# Mozard.net
KiCad netlist of a schematic drawn in EAGLE
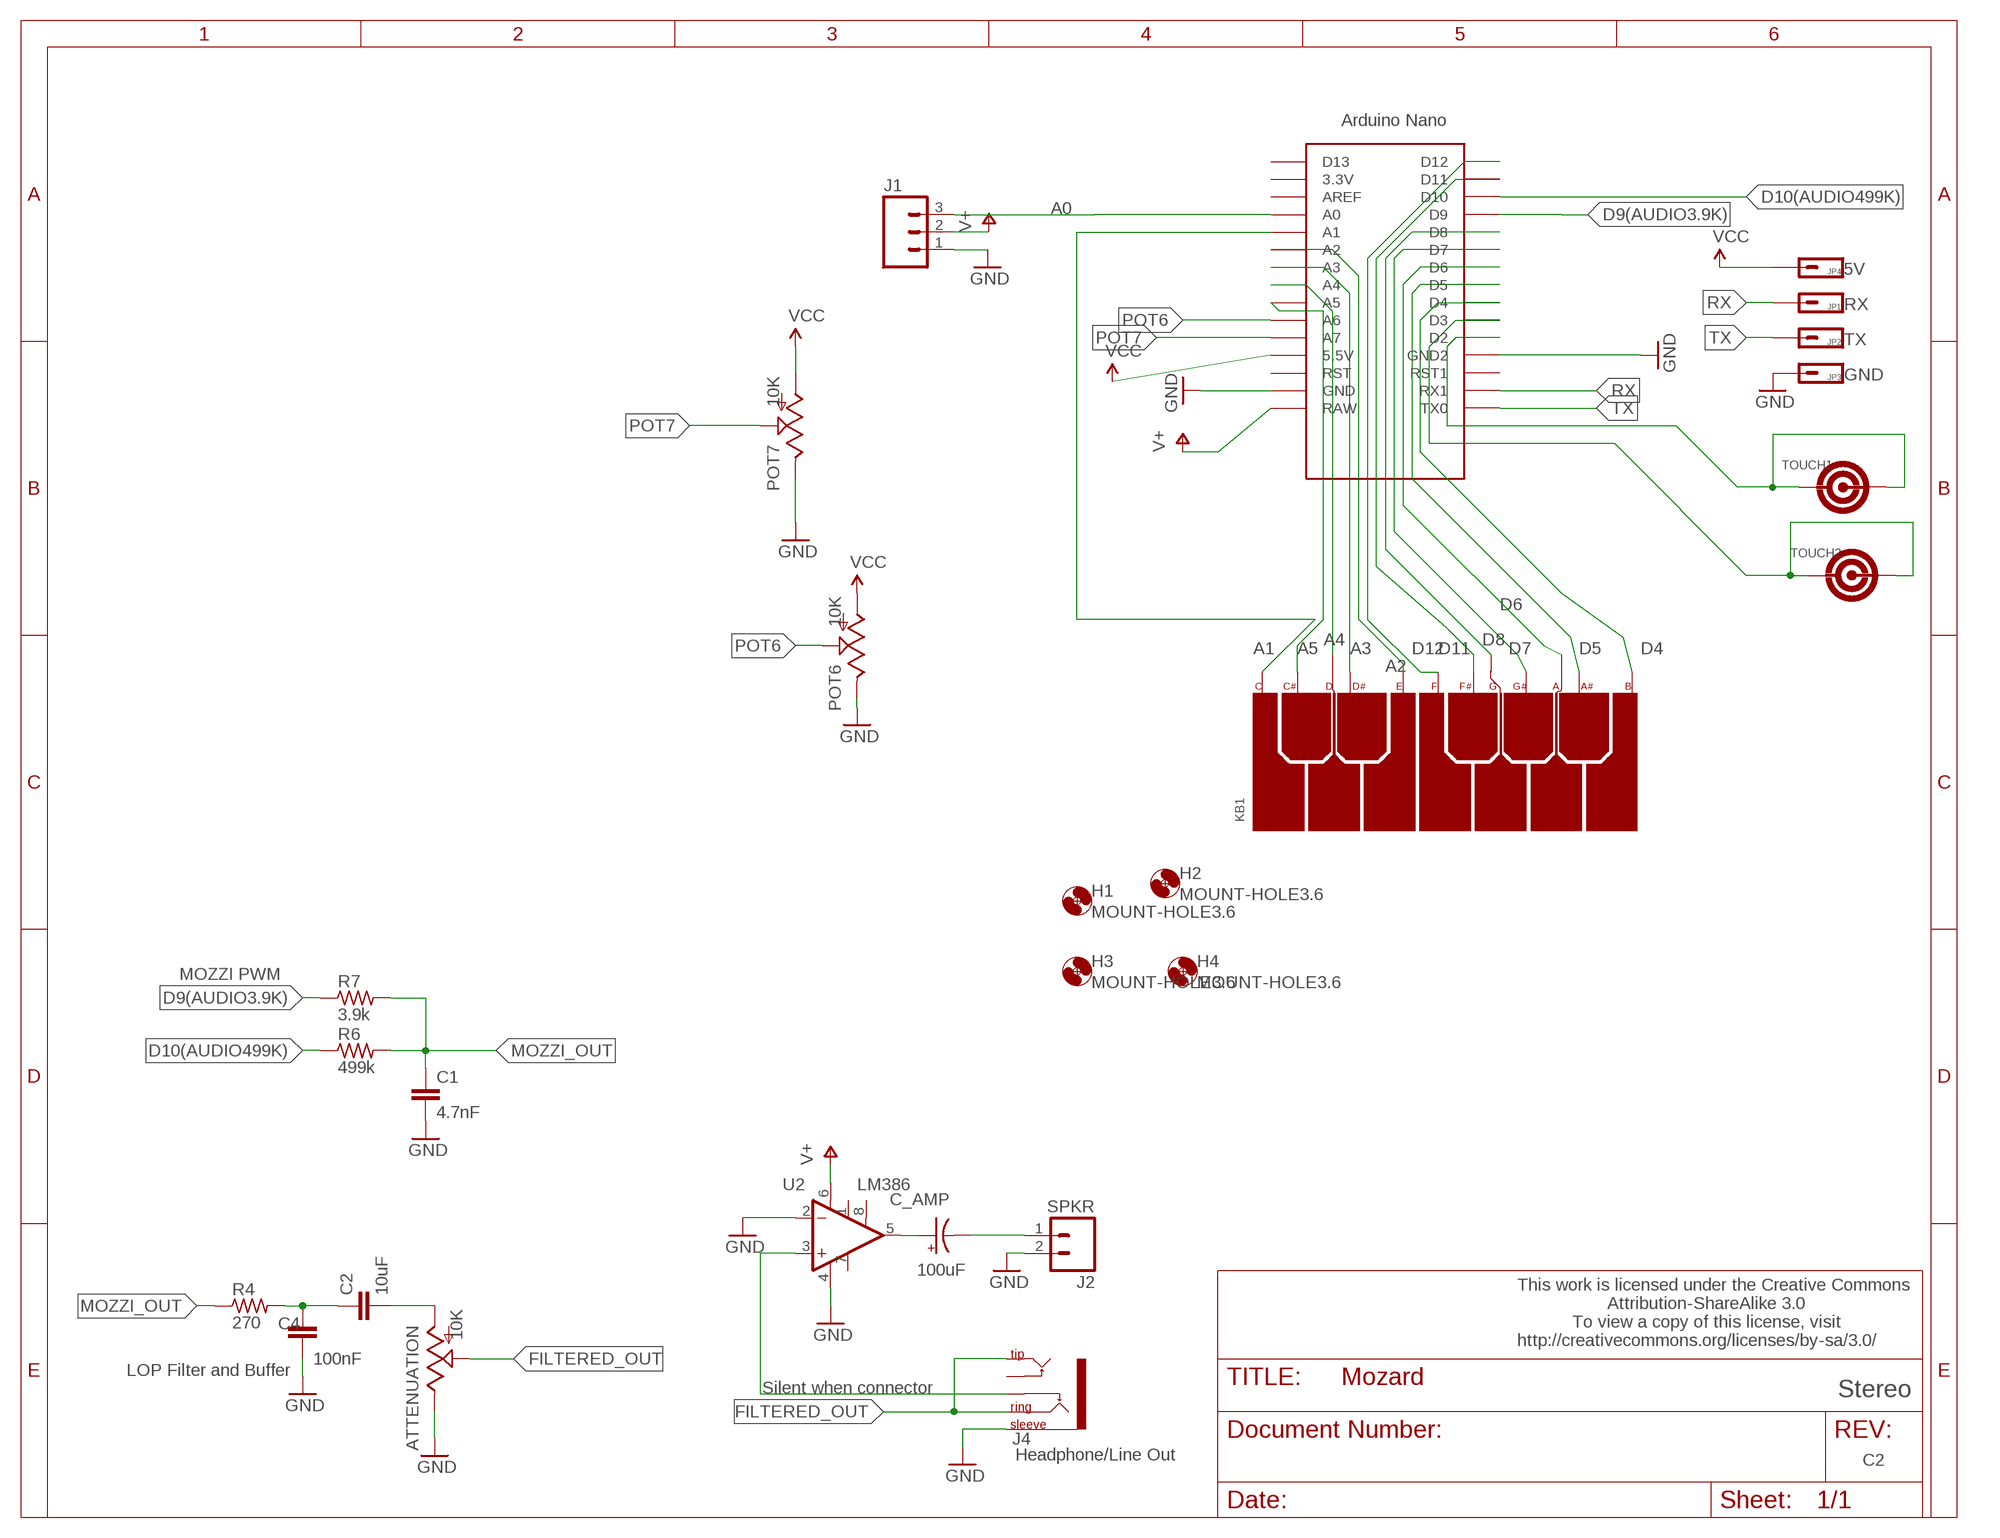
[diagram p0: schematic, sheet 1]

(export (version "E")
  (design (tool "Eeschema 10.0.6"))
  (components
    (comp (ref "ATTENUATION")
      (value "10K")
      (footprint "eagle-import:ALPS_POT_KIT")
      (libsource (lib "eagle-import") (part "POTALPS-KIT"))
    )
    (comp (ref "C1")
      (value "4.7nF")
      (footprint "eagle-import:CAP-PTH-SMALL-KIT")
      (libsource (lib "eagle-import") (part "0.1UF-50V-20%(PTH)KIT-EZ"))
    )
    (comp (ref "C2")
      (value "10uF")
      (footprint "eagle-import:CAP-PTH-SMALL-KIT")
      (libsource (lib "eagle-import") (part "0.1UF-50V-20%(PTH)KIT-EZ"))
    )
    (comp (ref "C4")
      (value "100nF")
      (footprint "eagle-import:CAP-PTH-SMALL-KIT")
      (libsource (lib "eagle-import") (part "0.1UF-50V-20%(PTH)KIT-EZ"))
    )
    (comp (ref "C_AMP")
      (value "100uF")
      (footprint "eagle-import:CPOL-RADIAL-10UF-25V")
      (libsource (lib "eagle-import") (part "CPOL-RADIAL-10UF-25V"))
    )
    (comp (ref "H1")
      (value "MOUNT-HOLE3.6")
      (footprint "eagle-import:3,6")
      (libsource (lib "eagle-import") (part "MOUNT-HOLE3.6"))
    )
    (comp (ref "H2")
      (value "MOUNT-HOLE3.6")
      (footprint "eagle-import:3,6")
      (libsource (lib "eagle-import") (part "MOUNT-HOLE3.6"))
    )
    (comp (ref "H3")
      (value "MOUNT-HOLE3.6")
      (footprint "eagle-import:3,6")
      (libsource (lib "eagle-import") (part "MOUNT-HOLE3.6"))
    )
    (comp (ref "H4")
      (value "MOUNT-HOLE3.6")
      (footprint "eagle-import:3,6")
      (libsource (lib "eagle-import") (part "MOUNT-HOLE3.6"))
    )
    (comp (ref "J1")
      (value "M03SCREW")
      (footprint "eagle-import:SCREWTERMINAL-3.5MM-3")
      (libsource (lib "eagle-import") (part "M03SCREW"))
    )
    (comp (ref "J2")
      (value "SPKR")
      (footprint "eagle-import:SCREWTERMINAL-3.5MM-2")
      (libsource (lib "eagle-import") (part "M023.5MM"))
    )
    (comp (ref "J4")
      (value "Headphone/Line Out")
      (footprint "eagle-import:AUDIO-JACK")
      (libsource (lib "eagle-import") (part "AUDIO-JACKPTH"))
    )
    (comp (ref "JP1")
      (value "RX")
      (footprint "eagle-import:1X01_SIDE_NAME")
      (libsource (lib "eagle-import") (part "HEADER-1X1"))
    )
    (comp (ref "JP2")
      (value "TX")
      (footprint "eagle-import:1X01_SIDE_NAME")
      (libsource (lib "eagle-import") (part "HEADER-1X1"))
    )
    (comp (ref "JP3")
      (value "GND")
      (footprint "eagle-import:1X01_SIDE_NAME")
      (libsource (lib "eagle-import") (part "HEADER-1X1"))
    )
    (comp (ref "JP4")
      (value "5V")
      (footprint "eagle-import:1X01_SIDE_NAME")
      (libsource (lib "eagle-import") (part "HEADER-1X1"))
    )
    (comp (ref "KB1")
      (value "PCB-KEYBOARD4")
      (footprint "eagle-import:PCB-KEYBOARD4")
      (libsource (lib "eagle-import") (part "PCB-KEYBOARD4"))
    )
    (comp (ref "POT6")
      (value "10K")
      (footprint "eagle-import:ALPS_POT_KIT")
      (libsource (lib "eagle-import") (part "POTALPS-KIT"))
    )
    (comp (ref "POT7")
      (value "10K")
      (footprint "eagle-import:ALPS_POT_KIT")
      (libsource (lib "eagle-import") (part "POTALPS-KIT"))
    )
    (comp (ref "R4")
      (value "270")
      (footprint "eagle-import:0204_7")
      (libsource (lib "eagle-import") (part "R-US_0204/7"))
    )
    (comp (ref "R6")
      (value "499k")
      (footprint "eagle-import:0204_7")
      (libsource (lib "eagle-import") (part "R-US_0204/7"))
    )
    (comp (ref "R7")
      (value "3.9k")
      (footprint "eagle-import:0204_7")
      (libsource (lib "eagle-import") (part "R-US_0204/7"))
    )
    (comp (ref "TOUCH1")
      (value "PCB-TOUCHPAD2")
      (footprint "eagle-import:PCB-TOUCHPAD2")
      (libsource (lib "eagle-import") (part "PCB-TOUCHPAD2"))
    )
    (comp (ref "TOUCH2")
      (value "PCB-TOUCHPAD2")
      (footprint "eagle-import:PCB-TOUCHPAD2")
      (libsource (lib "eagle-import") (part "PCB-TOUCHPAD2"))
    )
    (comp (ref "U$1")
      (value "NANO")
      (footprint "eagle-import:NANO")
      (libsource (lib "eagle-import") (part "NANO"))
    )
    (comp (ref "U2")
      (value "LM386")
      (footprint "eagle-import:DIP08")
      (libsource (lib "eagle-import") (part "LM386"))
    )
  )
  (nets
    (net (code "1") (name "/A0") (class "Default")
      (node (ref "J1") (pin "3") (pinfunction "3_3") (pintype "passive"))
      (node (ref "U$1") (pin "A0") (pinfunction "A0_A0") (pintype "bidirectional"))
    )
    (net (code "2") (name "/A1") (class "Default")
      (node (ref "KB1") (pin "C") (pinfunction "C_C") (pintype "bidirectional"))
      (node (ref "U$1") (pin "A1") (pinfunction "A1_A1") (pintype "bidirectional"))
    )
    (net (code "3") (name "/A2") (class "Default")
      (node (ref "KB1") (pin "E") (pinfunction "E_E") (pintype "bidirectional"))
      (node (ref "U$1") (pin "A2") (pinfunction "A2_A2") (pintype "bidirectional"))
    )
    (net (code "4") (name "/A3") (class "Default")
      (node (ref "KB1") (pin "D#") (pinfunction "D#_D#") (pintype "bidirectional"))
      (node (ref "U$1") (pin "A3") (pinfunction "A3_A3") (pintype "bidirectional"))
    )
    (net (code "5") (name "/A4") (class "Default")
      (node (ref "KB1") (pin "D") (pinfunction "D_D") (pintype "bidirectional"))
      (node (ref "U$1") (pin "A4") (pinfunction "A4_A4") (pintype "bidirectional"))
    )
    (net (code "6") (name "/A5") (class "Default")
      (node (ref "KB1") (pin "C#") (pinfunction "C#_C#") (pintype "bidirectional"))
      (node (ref "U$1") (pin "A5") (pinfunction "A5_A5") (pintype "bidirectional"))
    )
    (net (code "7") (name "/D4") (class "Default")
      (node (ref "KB1") (pin "B") (pinfunction "B_B") (pintype "bidirectional"))
      (node (ref "U$1") (pin "D4") (pinfunction "D4_D4") (pintype "bidirectional"))
    )
    (net (code "8") (name "/D5") (class "Default")
      (node (ref "KB1") (pin "A#") (pinfunction "A#_A#") (pintype "bidirectional"))
      (node (ref "U$1") (pin "D5") (pinfunction "D5_D5") (pintype "bidirectional"))
    )
    (net (code "9") (name "/D6") (class "Default")
      (node (ref "KB1") (pin "A") (pinfunction "A_A") (pintype "bidirectional"))
      (node (ref "U$1") (pin "D6") (pinfunction "D6_D6") (pintype "bidirectional"))
    )
    (net (code "10") (name "/D7") (class "Default")
      (node (ref "KB1") (pin "G#") (pinfunction "G#_G#") (pintype "bidirectional"))
      (node (ref "U$1") (pin "D7") (pinfunction "D7_D7") (pintype "bidirectional"))
    )
    (net (code "11") (name "/D8") (class "Default")
      (node (ref "KB1") (pin "G") (pinfunction "G_G") (pintype "bidirectional"))
      (node (ref "U$1") (pin "D8") (pinfunction "D8_D8") (pintype "bidirectional"))
    )
    (net (code "12") (name "/D11") (class "Default")
      (node (ref "KB1") (pin "F#") (pinfunction "F#_F#") (pintype "bidirectional"))
      (node (ref "U$1") (pin "D11") (pinfunction "D11_D11") (pintype "bidirectional"))
    )
    (net (code "13") (name "/D12") (class "Default")
      (node (ref "KB1") (pin "F") (pinfunction "F_F") (pintype "bidirectional"))
      (node (ref "U$1") (pin "D12") (pinfunction "D12_D12") (pintype "bidirectional"))
    )
    (net (code "14") (name "D9(AUDIO3.9K)") (class "Default")
      (node (ref "R7") (pin "1") (pinfunction "1_1") (pintype "passive"))
      (node (ref "U$1") (pin "D9") (pinfunction "D9_D9") (pintype "bidirectional"))
    )
    (net (code "15") (name "D10(AUDIO499K)") (class "Default")
      (node (ref "R6") (pin "1") (pinfunction "1_1") (pintype "passive"))
      (node (ref "U$1") (pin "D10") (pinfunction "D10_D10") (pintype "bidirectional"))
    )
    (net (code "16") (name "FILTERED_OUT") (class "Default")
      (node (ref "ATTENUATION") (pin "P$2") (pinfunction "S_P$2") (pintype "passive"))
      (node (ref "J4") (pin "RING") (pinfunction "RING_RING") (pintype "bidirectional"))
      (node (ref "J4") (pin "TIP") (pinfunction "TIP_TIP") (pintype "bidirectional"))
    )
    (net (code "17") (name "GND") (class "Default")
      (node (ref "ATTENUATION") (pin "P$1") (pinfunction "E_P$1") (pintype "passive"))
      (node (ref "C1") (pin "2") (pinfunction "2_2") (pintype "passive"))
      (node (ref "C4") (pin "2") (pinfunction "2_2") (pintype "passive"))
      (node (ref "J1") (pin "1") (pinfunction "1_1") (pintype "passive"))
      (node (ref "J2") (pin "2") (pinfunction "2_2") (pintype "passive"))
      (node (ref "J4") (pin "SLEEVE") (pinfunction "SLEEVE_SLEEVE") (pintype "bidirectional"))
      (node (ref "JP3") (pin "1") (pinfunction "1_1") (pintype "passive"))
      (node (ref "POT6") (pin "P$1") (pinfunction "E_P$1") (pintype "passive"))
      (node (ref "POT7") (pin "P$1") (pinfunction "E_P$1") (pintype "passive"))
      (node (ref "U$1") (pin "GND") (pinfunction "GND_GND") (pintype "bidirectional"))
      (node (ref "U$1") (pin "GND1") (pinfunction "GND2_GND1") (pintype "bidirectional"))
      (node (ref "U2") (pin "2") (pinfunction "-IN_2") (pintype "input"))
      (node (ref "U2") (pin "4") (pinfunction "V-_4") (pintype "power_in"))
    )
    (net (code "18") (name "MOZZI_OUT") (class "Default")
      (node (ref "C1") (pin "1") (pinfunction "1_1") (pintype "passive"))
      (node (ref "R4") (pin "1") (pinfunction "1_1") (pintype "passive"))
      (node (ref "R6") (pin "2") (pinfunction "2_2") (pintype "passive"))
      (node (ref "R7") (pin "2") (pinfunction "2_2") (pintype "passive"))
    )
    (net (code "19") (name "Net-(ATTENUATION-A)") (class "Default")
      (node (ref "ATTENUATION") (pin "P$3") (pinfunction "A_P$3") (pintype "passive"))
      (node (ref "C2") (pin "2") (pinfunction "2_2") (pintype "passive"))
    )
    (net (code "20") (name "Net-(C2-Pad1)") (class "Default")
      (node (ref "C2") (pin "1") (pinfunction "1_1") (pintype "passive"))
      (node (ref "C4") (pin "1") (pinfunction "1_1") (pintype "passive"))
      (node (ref "R4") (pin "2") (pinfunction "2_2") (pintype "passive"))
    )
    (net (code "21") (name "Net-(C_AMP-Pad-)") (class "Default")
      (node (ref "C_AMP") (pin "-") (pinfunction "-_-") (pintype "passive"))
      (node (ref "J2") (pin "1") (pinfunction "1_1") (pintype "passive"))
    )
    (net (code "22") (name "Net-(TOUCH1-Pad1)") (class "Default")
      (node (ref "TOUCH1") (pin "1") (pinfunction "1_1") (pintype "bidirectional"))
      (node (ref "TOUCH1") (pin "2") (pinfunction "2_2") (pintype "bidirectional"))
      (node (ref "U$1") (pin "D2") (pinfunction "D2_D2") (pintype "bidirectional"))
    )
    (net (code "23") (name "Net-(TOUCH2-Pad1)") (class "Default")
      (node (ref "TOUCH2") (pin "1") (pinfunction "1_1") (pintype "bidirectional"))
      (node (ref "TOUCH2") (pin "2") (pinfunction "2_2") (pintype "bidirectional"))
      (node (ref "U$1") (pin "D3") (pinfunction "D3_D3") (pintype "bidirectional"))
    )
    (net (code "24") (name "Net-(U2-+IN)") (class "Default")
      (node (ref "J4") (pin "RSH") (pinfunction "RSH_RSH") (pintype "bidirectional"))
      (node (ref "U2") (pin "3") (pinfunction "+IN_3") (pintype "input"))
    )
    (net (code "25") (name "Net-(U2-OUT)") (class "Default")
      (node (ref "C_AMP") (pin "+") (pinfunction "+_+") (pintype "passive"))
      (node (ref "U2") (pin "5") (pinfunction "OUT_5") (pintype "output"))
    )
    (net (code "26") (name "POT6") (class "Default")
      (node (ref "POT6") (pin "P$2") (pinfunction "S_P$2") (pintype "passive"))
      (node (ref "U$1") (pin "A6") (pinfunction "A6_A6") (pintype "bidirectional"))
    )
    (net (code "27") (name "POT7") (class "Default")
      (node (ref "POT7") (pin "P$2") (pinfunction "S_P$2") (pintype "passive"))
      (node (ref "U$1") (pin "A7") (pinfunction "A7_A7") (pintype "bidirectional"))
    )
    (net (code "28") (name "RX") (class "Default")
      (node (ref "JP1") (pin "1") (pinfunction "1_1") (pintype "passive"))
      (node (ref "U$1") (pin "RX1") (pinfunction "RX1_RX1") (pintype "bidirectional"))
    )
    (net (code "29") (name "TX") (class "Default")
      (node (ref "JP2") (pin "1") (pinfunction "1_1") (pintype "passive"))
      (node (ref "U$1") (pin "TX0") (pinfunction "TX0_TX0") (pintype "bidirectional"))
    )
    (net (code "30") (name "V+") (class "Default")
      (node (ref "J1") (pin "2") (pinfunction "2_2") (pintype "passive"))
      (node (ref "U$1") (pin "RAW") (pinfunction "RAW_RAW") (pintype "bidirectional"))
      (node (ref "U2") (pin "6") (pinfunction "V+_6") (pintype "power_in"))
    )
    (net (code "31") (name "VCC") (class "Default")
      (node (ref "JP4") (pin "1") (pinfunction "1_1") (pintype "passive"))
      (node (ref "POT6") (pin "P$3") (pinfunction "A_P$3") (pintype "passive"))
      (node (ref "POT7") (pin "P$3") (pinfunction "A_P$3") (pintype "passive"))
      (node (ref "U$1") (pin "5V") (pinfunction "5.5V_5V") (pintype "bidirectional"))
    )
    (net (code "32") (name "unconnected-(J4-PadTSH)") (class "Default")
      (node (ref "J4") (pin "TSH") (pinfunction "TSH_TSH") (pintype "bidirectional"))
    )
    (net (code "33") (name "unconnected-(U$1-Pad3.3V)") (class "Default")
      (node (ref "U$1") (pin "3.3V") (pinfunction "3.3V_3.3V") (pintype "bidirectional"))
    )
    (net (code "34") (name "unconnected-(U$1-PadAREF)") (class "Default")
      (node (ref "U$1") (pin "AREF") (pinfunction "AREF_AREF") (pintype "bidirectional"))
    )
    (net (code "35") (name "unconnected-(U$1-PadD13)") (class "Default")
      (node (ref "U$1") (pin "D13") (pinfunction "D13_D13") (pintype "bidirectional"))
    )
    (net (code "36") (name "unconnected-(U$1-PadRST)") (class "Default")
      (node (ref "U$1") (pin "RST") (pinfunction "RST_RST") (pintype "bidirectional"))
    )
    (net (code "37") (name "unconnected-(U$1-PadRST1)") (class "Default")
      (node (ref "U$1") (pin "RST1") (pinfunction "RST1_RST1") (pintype "bidirectional"))
    )
    (net (code "38") (name "unconnected-(U2-BP-Pad7)") (class "Default")
      (node (ref "U2") (pin "7") (pinfunction "BP_7") (pintype "bidirectional"))
    )
    (net (code "39") (name "unconnected-(U2-GAIN-Pad1)") (class "Default")
      (node (ref "U2") (pin "1") (pinfunction "GAIN_1") (pintype "bidirectional"))
    )
    (net (code "40") (name "unconnected-(U2-GAIN-Pad8)") (class "Default")
      (node (ref "U2") (pin "8") (pinfunction "GAIN_8") (pintype "bidirectional"))
    )
  )
)
